# Sheet1.net
KiCad netlist of a schematic drawn in Altium Designer
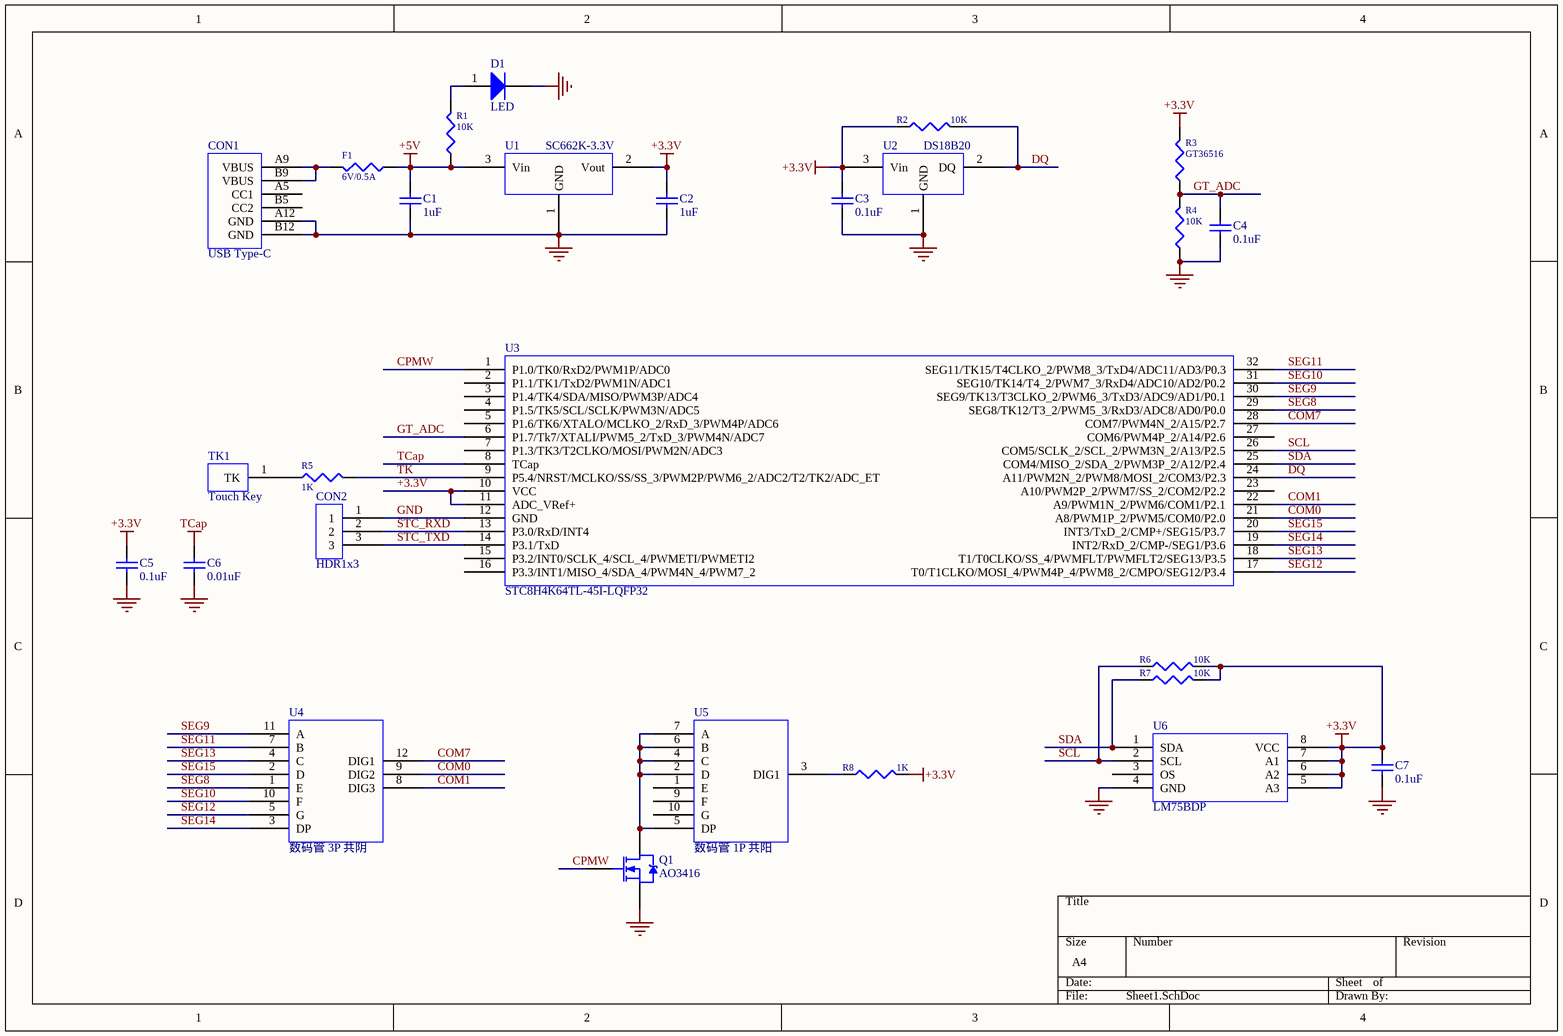
[diagram p0: Sheet1.SchDoc]

(export (version "E")
  (design (tool "Eeschema 10.0.6"))
  (components
    (comp (ref "C1")
      (value "1uF")
      (footprint "0603_C")
      (description "贴片电容")
      (libsource (lib "Miscellaneous Devices LC") (part "0603 100nF (104) 10% 50V"))
    )
    (comp (ref "C2")
      (value "1uF")
      (footprint "0603_C")
      (description "贴片电容")
      (libsource (lib "Miscellaneous Devices LC") (part "0603 100nF (104) 10% 50V"))
    )
    (comp (ref "C3")
      (value "0.1uF")
      (footprint "0603_C")
      (description "贴片电容")
      (libsource (lib "Miscellaneous Devices LC") (part "0603 100nF (104) 10% 50V"))
    )
    (comp (ref "C4")
      (value "0.1uF")
      (footprint "0603_C")
      (description "贴片电容")
      (libsource (lib "Miscellaneous Devices LC") (part "0603 100nF (104) 10% 50V"))
    )
    (comp (ref "C5")
      (value "0.1uF")
      (footprint "0603_C")
      (description "贴片电容")
      (libsource (lib "Miscellaneous Devices LC") (part "0603 100nF (104) 10% 50V"))
    )
    (comp (ref "C6")
      (value "0.01uF")
      (footprint "0603_C")
      (description "贴片电容")
      (libsource (lib "Miscellaneous Devices LC") (part "0603 100nF (104) 10% 50V"))
    )
    (comp (ref "C7")
      (value "0.1uF")
      (footprint "0603_C")
      (description "贴片电容")
      (libsource (lib "Miscellaneous Devices LC") (part "0603 100nF (104) 10% 50V"))
    )
    (comp (ref "CON1")
      (value "USB Type-C")
      (footprint "Type-C 6P")
      (libsource (lib "Schlib1") (part "USB Type-C"))
    )
    (comp (ref "CON2") (value "HDR1x3") (footprint "HDR1x3") (libsource (lib "Schlib1") (part "HDR1x3")))
    (comp (ref "D1")
      (value "LED")
      (footprint "0603_LED_S1")
      (description "二极管")
      (libsource (lib "Schlib1") (part "Diode"))
    )
    (comp (ref "F1")
      (value "6V/0.5A")
      (footprint "0603_L")
      (description "Resistor")
      (libsource (lib "*") (part "RES"))
    )
    (comp (ref "Q1")
      (value "AO3416")
      (footprint "SOT-23(SOT-23-3)")
      (description "N-Channel Power MOSFET")
      (fields (field (name "PUBLISHER") "Altium Limited"))
      (libsource (lib "Schlib1") (part "AO3416"))
    )
    (comp (ref "R1")
      (value "10K")
      (footprint "0603_R")
      (description "Resistor")
      (libsource (lib "*") (part "RES"))
    )
    (comp (ref "R2")
      (value "10K")
      (footprint "0603_R")
      (description "Resistor")
      (libsource (lib "*") (part "RES"))
    )
    (comp (ref "R3")
      (value "GT36516")
      (footprint "1210_R")
      (description "Resistor")
      (libsource (lib "*") (part "RES"))
    )
    (comp (ref "R4")
      (value "10K")
      (footprint "0603_R")
      (description "Resistor")
      (libsource (lib "*") (part "RES"))
    )
    (comp (ref "R5")
      (value "1K")
      (footprint "0603_R")
      (description "Resistor")
      (libsource (lib "*") (part "RES"))
    )
    (comp (ref "R6")
      (value "10K")
      (footprint "0603_R")
      (description "Resistor")
      (libsource (lib "*") (part "RES"))
    )
    (comp (ref "R7")
      (value "10K")
      (footprint "0603_R")
      (description "Resistor")
      (libsource (lib "*") (part "RES"))
    )
    (comp (ref "R8")
      (value "1K")
      (footprint "0603_R")
      (description "Resistor")
      (libsource (lib "*") (part "RES"))
    )
    (comp (ref "TK1")
      (value "Touch Key")
      (footprint "TouchKeyD6")
      (libsource (lib "Schlib1") (part "Touch Key"))
    )
    (comp (ref "U1")
      (value "SC662K-3.3V")
      (footprint "SOT-23(SOT-23-3)")
      (libsource (lib "Schlib1") (part "AMS1117 3.3V"))
    )
    (comp (ref "U2")
      (value "DS18B20")
      (footprint "TO-92(TO-92-3)")
      (libsource (lib "Schlib1") (part "DS18B20"))
    )
    (comp (ref "U3")
      (value "STC8H4K64TL-45I-LQFP32")
      (footprint "LQFP-32_7x7x08P")
      (libsource (lib "Schlib1") (part "STC8H4K64TL-45I-LQFP32"))
    )
    (comp (ref "U4") (value "数码管 3P 共阴") (footprint "0.56寸 3位") (libsource (lib "Schlib1") (part "数码管 3P")))
    (comp (ref "U5") (value "数码管 1P 共阳") (footprint "0.56寸 1位") (libsource (lib "Schlib1") (part "数码管 1P")))
    (comp (ref "U6") (value "LM75BDP") (footprint "MSOP-8") (libsource (lib "Schlib1") (part "LM75BDP")))
  )
  (nets
    (net (code "1") (name "+3.3V") (class "Default")
      (node (ref "C2") (pin "2") (pinfunction "2_2") (pintype "passive"))
      (node (ref "C3") (pin "2") (pinfunction "2_2") (pintype "passive"))
      (node (ref "C5") (pin "2") (pinfunction "2_2") (pintype "passive"))
      (node (ref "C7") (pin "2") (pinfunction "2_2") (pintype "passive"))
      (node (ref "R2") (pin "2") (pinfunction "BOT_2") (pintype "passive"))
      (node (ref "R3") (pin "1") (pinfunction "TOP_1") (pintype "passive"))
      (node (ref "R6") (pin "1") (pinfunction "TOP_1") (pintype "passive"))
      (node (ref "R7") (pin "1") (pinfunction "TOP_1") (pintype "passive"))
      (node (ref "R8") (pin "1") (pinfunction "TOP_1") (pintype "passive"))
      (node (ref "U1") (pin "2") (pinfunction "Vout_2") (pintype "passive"))
      (node (ref "U2") (pin "3") (pinfunction "Vin_3") (pintype "passive"))
      (node (ref "U3") (pin "10") (pinfunction "VCC_10") (pintype "passive"))
      (node (ref "U3") (pin "11") (pinfunction "ADC_VRef+_11") (pintype "passive"))
      (node (ref "U6") (pin "5") (pinfunction "A3_5") (pintype "passive"))
      (node (ref "U6") (pin "6") (pinfunction "A2_6") (pintype "passive"))
      (node (ref "U6") (pin "7") (pinfunction "A1_7") (pintype "passive"))
      (node (ref "U6") (pin "8") (pinfunction "VCC_8") (pintype "passive"))
    )
    (net (code "2") (name "+5V") (class "Default")
      (node (ref "C1") (pin "2") (pinfunction "2_2") (pintype "passive"))
      (node (ref "F1") (pin "2") (pinfunction "BOT_2") (pintype "passive"))
      (node (ref "R1") (pin "2") (pinfunction "BOT_2") (pintype "passive"))
      (node (ref "U1") (pin "3") (pinfunction "Vin_3") (pintype "passive"))
    )
    (net (code "3") (name "/COM0") (class "Default")
      (node (ref "U3") (pin "21") (pinfunction "A8/PWM1P_2/PWM5/COM0/P2.0_21") (pintype "passive"))
      (node (ref "U4") (pin "9") (pinfunction "DIG2_9") (pintype "passive"))
    )
    (net (code "4") (name "/COM1") (class "Default")
      (node (ref "U3") (pin "22") (pinfunction "A9/PWM1N_2/PWM6/COM1/P2.1_22") (pintype "passive"))
      (node (ref "U4") (pin "8") (pinfunction "DIG3_8") (pintype "passive"))
    )
    (net (code "5") (name "/COM7") (class "Default")
      (node (ref "U3") (pin "28") (pinfunction "COM7/PWM4N_2/A15/P2.7_28") (pintype "passive"))
      (node (ref "U4") (pin "12") (pinfunction "DIG1_12") (pintype "passive"))
    )
    (net (code "6") (name "/CPMW") (class "Default")
      (node (ref "Q1") (pin "1") (pinfunction "G_1") (pintype "passive"))
      (node (ref "U3") (pin "1") (pinfunction "P1.0/TK0/RxD2/PWM1P/ADC0_1") (pintype "passive"))
    )
    (net (code "7") (name "/DQ") (class "Default")
      (node (ref "R2") (pin "1") (pinfunction "TOP_1") (pintype "passive"))
      (node (ref "U2") (pin "2") (pinfunction "DQ_2") (pintype "passive"))
      (node (ref "U3") (pin "24") (pinfunction "A11/PWM2N_2/PWM8/MOSI_2/COM3/P2.3_24") (pintype "passive"))
    )
    (net (code "8") (name "/GT_ADC") (class "Default")
      (node (ref "C4") (pin "2") (pinfunction "2_2") (pintype "passive"))
      (node (ref "R3") (pin "2") (pinfunction "BOT_2") (pintype "passive"))
      (node (ref "R4") (pin "1") (pinfunction "TOP_1") (pintype "passive"))
      (node (ref "U3") (pin "6") (pinfunction "P1.7/Tk7/XTALI/PWM5_2/TxD_3/PWM4N/ADC7_6") (pintype "passive"))
    )
    (net (code "9") (name "/SCL") (class "Default")
      (node (ref "R6") (pin "2") (pinfunction "BOT_2") (pintype "passive"))
      (node (ref "U3") (pin "26") (pinfunction "COM5/SCLK_2/SCL_2/PWM3N_2/A13/P2.5_26") (pintype "passive"))
      (node (ref "U6") (pin "2") (pinfunction "SCL_2") (pintype "passive"))
    )
    (net (code "10") (name "/SDA") (class "Default")
      (node (ref "R7") (pin "2") (pinfunction "BOT_2") (pintype "passive"))
      (node (ref "U3") (pin "25") (pinfunction "COM4/MISO_2/SDA_2/PWM3P_2/A12/P2.4_25") (pintype "passive"))
      (node (ref "U6") (pin "1") (pinfunction "SDA_1") (pintype "passive"))
    )
    (net (code "11") (name "/SEG8") (class "Default")
      (node (ref "U3") (pin "29") (pinfunction "SEG8/TK12/T3_2/PWM5_3/RxD3/ADC8/AD0/P0.0_29") (pintype "passive"))
      (node (ref "U4") (pin "1") (pinfunction "E_1") (pintype "passive"))
    )
    (net (code "12") (name "/SEG9") (class "Default")
      (node (ref "U3") (pin "30") (pinfunction "SEG9/TK13/T3CLKO_2/PWM6_3/TxD3/ADC9/AD1/P0.1_30") (pintype "passive"))
      (node (ref "U4") (pin "11") (pinfunction "A_11") (pintype "passive"))
    )
    (net (code "13") (name "/SEG10") (class "Default")
      (node (ref "U3") (pin "31") (pinfunction "SEG10/TK14/T4_2/PWM7_3/RxD4/ADC10/AD2/P0.2_31") (pintype "passive"))
      (node (ref "U4") (pin "10") (pinfunction "F_10") (pintype "passive"))
    )
    (net (code "14") (name "/SEG11") (class "Default")
      (node (ref "U3") (pin "32") (pinfunction "SEG11/TK15/T4CLKO_2/PWM8_3/TxD4/ADC11/AD3/P0.3_32") (pintype "passive"))
      (node (ref "U4") (pin "7") (pinfunction "B_7") (pintype "passive"))
    )
    (net (code "15") (name "/SEG12") (class "Default")
      (node (ref "U3") (pin "17") (pinfunction "T0/T1CLKO/MOSI_4/PWM4P_4/PWM8_2/CMPO/SEG12/P3.4_17") (pintype "passive"))
      (node (ref "U4") (pin "5") (pinfunction "G_5") (pintype "passive"))
    )
    (net (code "16") (name "/SEG13") (class "Default")
      (node (ref "U3") (pin "18") (pinfunction "T1/T0CLKO/SS_4/PWMFLT/PWMFLT2/SEG13/P3.5_18") (pintype "passive"))
      (node (ref "U4") (pin "4") (pinfunction "C_4") (pintype "passive"))
    )
    (net (code "17") (name "/SEG14") (class "Default")
      (node (ref "U3") (pin "19") (pinfunction "INT2/RxD_2/CMP-/SEG1/P3.6_19") (pintype "passive"))
      (node (ref "U4") (pin "3") (pinfunction "DP_3") (pintype "passive"))
    )
    (net (code "18") (name "/SEG15") (class "Default")
      (node (ref "U3") (pin "20") (pinfunction "INT3/TxD_2/CMP+/SEG15/P3.7_20") (pintype "passive"))
      (node (ref "U4") (pin "2") (pinfunction "D_2") (pintype "passive"))
    )
    (net (code "19") (name "/STC_RXD") (class "Default")
      (node (ref "CON2") (pin "2") (pinfunction "2_2") (pintype "passive"))
      (node (ref "U3") (pin "13") (pinfunction "P3.0/RxD/INT4_13") (pintype "passive"))
    )
    (net (code "20") (name "/STC_TXD") (class "Default")
      (node (ref "CON2") (pin "3") (pinfunction "3_3") (pintype "passive"))
      (node (ref "U3") (pin "14") (pinfunction "P3.1/TxD_14") (pintype "passive"))
    )
    (net (code "21") (name "/TK") (class "Default")
      (node (ref "R5") (pin "1") (pinfunction "TOP_1") (pintype "passive"))
      (node (ref "U3") (pin "9") (pinfunction "P5.4/NRST/MCLKO/SS/SS_3/PWM2P/PWM6_2/ADC2/T2/TK2/ADC_ET_9") (pintype "passive"))
    )
    (net (code "22") (name "GND") (class "Default")
      (node (ref "C1") (pin "1") (pinfunction "1_1") (pintype "passive"))
      (node (ref "C2") (pin "1") (pinfunction "1_1") (pintype "passive"))
      (node (ref "C3") (pin "1") (pinfunction "1_1") (pintype "passive"))
      (node (ref "C4") (pin "1") (pinfunction "1_1") (pintype "passive"))
      (node (ref "C5") (pin "1") (pinfunction "1_1") (pintype "passive"))
      (node (ref "C6") (pin "1") (pinfunction "1_1") (pintype "passive"))
      (node (ref "C7") (pin "1") (pinfunction "1_1") (pintype "passive"))
      (node (ref "CON1") (pin "A12") (pinfunction "GND_A12") (pintype "passive"))
      (node (ref "CON1") (pin "B12") (pinfunction "GND_B12") (pintype "passive"))
      (node (ref "CON2") (pin "1") (pinfunction "1_1") (pintype "passive"))
      (node (ref "D1") (pin "2") (pinfunction "K_2") (pintype "passive"))
      (node (ref "Q1") (pin "2") (pinfunction "S_2") (pintype "passive"))
      (node (ref "R4") (pin "2") (pinfunction "BOT_2") (pintype "passive"))
      (node (ref "U1") (pin "1") (pinfunction "GND_1") (pintype "passive"))
      (node (ref "U2") (pin "1") (pinfunction "GND_1") (pintype "passive"))
      (node (ref "U3") (pin "12") (pinfunction "GND_12") (pintype "passive"))
      (node (ref "U6") (pin "4") (pinfunction "GND_4") (pintype "passive"))
    )
    (net (code "23") (name "Net-(D1-A)") (class "Default")
      (node (ref "D1") (pin "1") (pinfunction "A_1") (pintype "passive"))
      (node (ref "R1") (pin "1") (pinfunction "TOP_1") (pintype "passive"))
    )
    (net (code "24") (name "Net-(F1-TOP)") (class "Default")
      (node (ref "CON1") (pin "A9") (pinfunction "VBUS_A9") (pintype "passive"))
      (node (ref "CON1") (pin "B9") (pinfunction "VBUS_B9") (pintype "passive"))
      (node (ref "F1") (pin "1") (pinfunction "TOP_1") (pintype "passive"))
    )
    (net (code "25") (name "Net-(Q1-D)") (class "Default")
      (node (ref "Q1") (pin "3") (pinfunction "D_3") (pintype "passive"))
      (node (ref "U5") (pin "2") (pinfunction "D_2") (pintype "passive"))
      (node (ref "U5") (pin "4") (pinfunction "C_4") (pintype "passive"))
      (node (ref "U5") (pin "5") (pinfunction "DP_5") (pintype "passive"))
      (node (ref "U5") (pin "6") (pinfunction "B_6") (pintype "passive"))
      (node (ref "U5") (pin "7") (pinfunction "A_7") (pintype "passive"))
    )
    (net (code "26") (name "Net-(R5-BOT)") (class "Default")
      (node (ref "R5") (pin "2") (pinfunction "BOT_2") (pintype "passive"))
      (node (ref "TK1") (pin "1") (pinfunction "TK_1") (pintype "passive"))
    )
    (net (code "27") (name "Net-(R8-BOT)") (class "Default")
      (node (ref "R8") (pin "2") (pinfunction "BOT_2") (pintype "passive"))
      (node (ref "U5") (pin "3") (pinfunction "DIG1_3") (pintype "passive"))
    )
    (net (code "28") (name "TCap") (class "Default")
      (node (ref "C6") (pin "2") (pinfunction "2_2") (pintype "passive"))
      (node (ref "U3") (pin "8") (pinfunction "TCap_8") (pintype "passive"))
    )
    (net (code "29") (name "unconnected-(CON1-CC1-PadA5)") (class "Default")
      (node (ref "CON1") (pin "A5") (pinfunction "CC1_A5") (pintype "passive"))
    )
    (net (code "30") (name "unconnected-(CON1-CC2-PadB5)") (class "Default")
      (node (ref "CON1") (pin "B5") (pinfunction "CC2_B5") (pintype "passive"))
    )
    (net (code "31") (name "unconnected-(U3-A10{slash}PWM2P_2{slash}PWM7{slash}SS_2{slash}COM2{slash}P2.2-Pad23)") (class "Default")
      (node (ref "U3") (pin "23") (pinfunction "A10/PWM2P_2/PWM7/SS_2/COM2/P2.2_23") (pintype "passive"))
    )
    (net (code "32") (name "unconnected-(U3-COM6{slash}PWM4P_2{slash}A14{slash}P2.6-Pad27)") (class "Default")
      (node (ref "U3") (pin "27") (pinfunction "COM6/PWM4P_2/A14/P2.6_27") (pintype "passive"))
    )
    (net (code "33") (name "unconnected-(U3-P1.1{slash}TK1{slash}TxD2{slash}PWM1N{slash}ADC1-Pad2)") (class "Default")
      (node (ref "U3") (pin "2") (pinfunction "P1.1/TK1/TxD2/PWM1N/ADC1_2") (pintype "passive"))
    )
    (net (code "34") (name "unconnected-(U3-P1.3{slash}TK3{slash}T2CLKO{slash}MOSI{slash}PWM2N{slash}ADC3-Pad7)") (class "Default")
      (node (ref "U3") (pin "7") (pinfunction "P1.3/TK3/T2CLKO/MOSI/PWM2N/ADC3_7") (pintype "passive"))
    )
    (net (code "35") (name "unconnected-(U3-P1.4{slash}TK4{slash}SDA{slash}MISO{slash}PWM3P{slash}ADC4-Pad3)") (class "Default")
      (node (ref "U3") (pin "3") (pinfunction "P1.4/TK4/SDA/MISO/PWM3P/ADC4_3") (pintype "passive"))
    )
    (net (code "36") (name "unconnected-(U3-P1.5{slash}TK5{slash}SCL{slash}SCLK{slash}PWM3N{slash}ADC5-Pad4)") (class "Default")
      (node (ref "U3") (pin "4") (pinfunction "P1.5/TK5/SCL/SCLK/PWM3N/ADC5_4") (pintype "passive"))
    )
    (net (code "37") (name "unconnected-(U3-P1.6{slash}TK6{slash}XTALO{slash}MCLKO_2{slash}RxD_3{slash}PWM4P{slash}ADC6-Pad5)") (class "Default")
      (node (ref "U3") (pin "5") (pinfunction "P1.6/TK6/XTALO/MCLKO_2/RxD_3/PWM4P/ADC6_5") (pintype "passive"))
    )
    (net (code "38") (name "unconnected-(U3-P3.2{slash}INT0{slash}SCLK_4{slash}SCL_4{slash}PWMETI{slash}PWMETI2-Pad15)") (class "Default")
      (node (ref "U3") (pin "15") (pinfunction "P3.2/INT0/SCLK_4/SCL_4/PWMETI/PWMETI2_15") (pintype "passive"))
    )
    (net (code "39") (name "unconnected-(U3-P3.3{slash}INT1{slash}MISO_4{slash}SDA_4{slash}PWM4N_4{slash}PWM7_2-Pad16)") (class "Default")
      (node (ref "U3") (pin "16") (pinfunction "P3.3/INT1/MISO_4/SDA_4/PWM4N_4/PWM7_2_16") (pintype "passive"))
    )
    (net (code "40") (name "unconnected-(U5-E-Pad1)") (class "Default")
      (node (ref "U5") (pin "1") (pinfunction "E_1") (pintype "passive"))
    )
    (net (code "41") (name "unconnected-(U5-F-Pad9)") (class "Default")
      (node (ref "U5") (pin "9") (pinfunction "F_9") (pintype "passive"))
    )
    (net (code "42") (name "unconnected-(U5-G-Pad10)") (class "Default")
      (node (ref "U5") (pin "10") (pinfunction "G_10") (pintype "passive"))
    )
    (net (code "43") (name "unconnected-(U6-OS-Pad3)") (class "Default")
      (node (ref "U6") (pin "3") (pinfunction "OS_3") (pintype "passive"))
    )
  )
)
